# connectors.net
KiCad netlist of a schematic drawn in Altium Designer
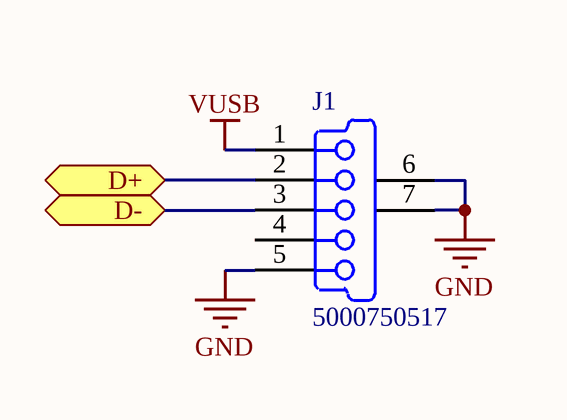
[diagram p0: connectors.SchDoc]

(export (version "E")
  (design (tool "Eeschema 10.0.6"))
  (components
    (comp (ref "J1")
      (value "5000750517")
      (footprint "5000750517")
      (fields (field (name "PUBLISHER") "Altium Limited"))
      (libsource (lib "Molex Serial Bus Mini USB") (part "5000750517"))
    )
  )
  (nets
    (net (code "1") (name "/D+") (class "Default")
      (node (ref "J1") (pin "2") (pinfunction "D-_2") (pintype "passive"))
    )
    (net (code "2") (name "/D-") (class "Default")
      (node (ref "J1") (pin "3") (pinfunction "D+_3") (pintype "passive"))
    )
    (net (code "3") (name "GND") (class "Default")
      (node (ref "J1") (pin "5") (pinfunction "GND_5") (pintype "passive"))
      (node (ref "J1") (pin "6") (pinfunction "MH1_6") (pintype "passive"))
      (node (ref "J1") (pin "7") (pinfunction "MH2_7") (pintype "passive"))
    )
    (net (code "4") (name "VUSB") (class "Default")
      (node (ref "J1") (pin "1") (pinfunction "V_BUS_1") (pintype "passive"))
    )
    (net (code "5") (name "unconnected-(J1-ID-Pad4)") (class "Default")
      (node (ref "J1") (pin "4") (pinfunction "ID_4") (pintype "passive"))
    )
  )
)
